# MAGIC-HOOVER-TRANS.net
KiCad netlist of a schematic drawn in EasyEDA
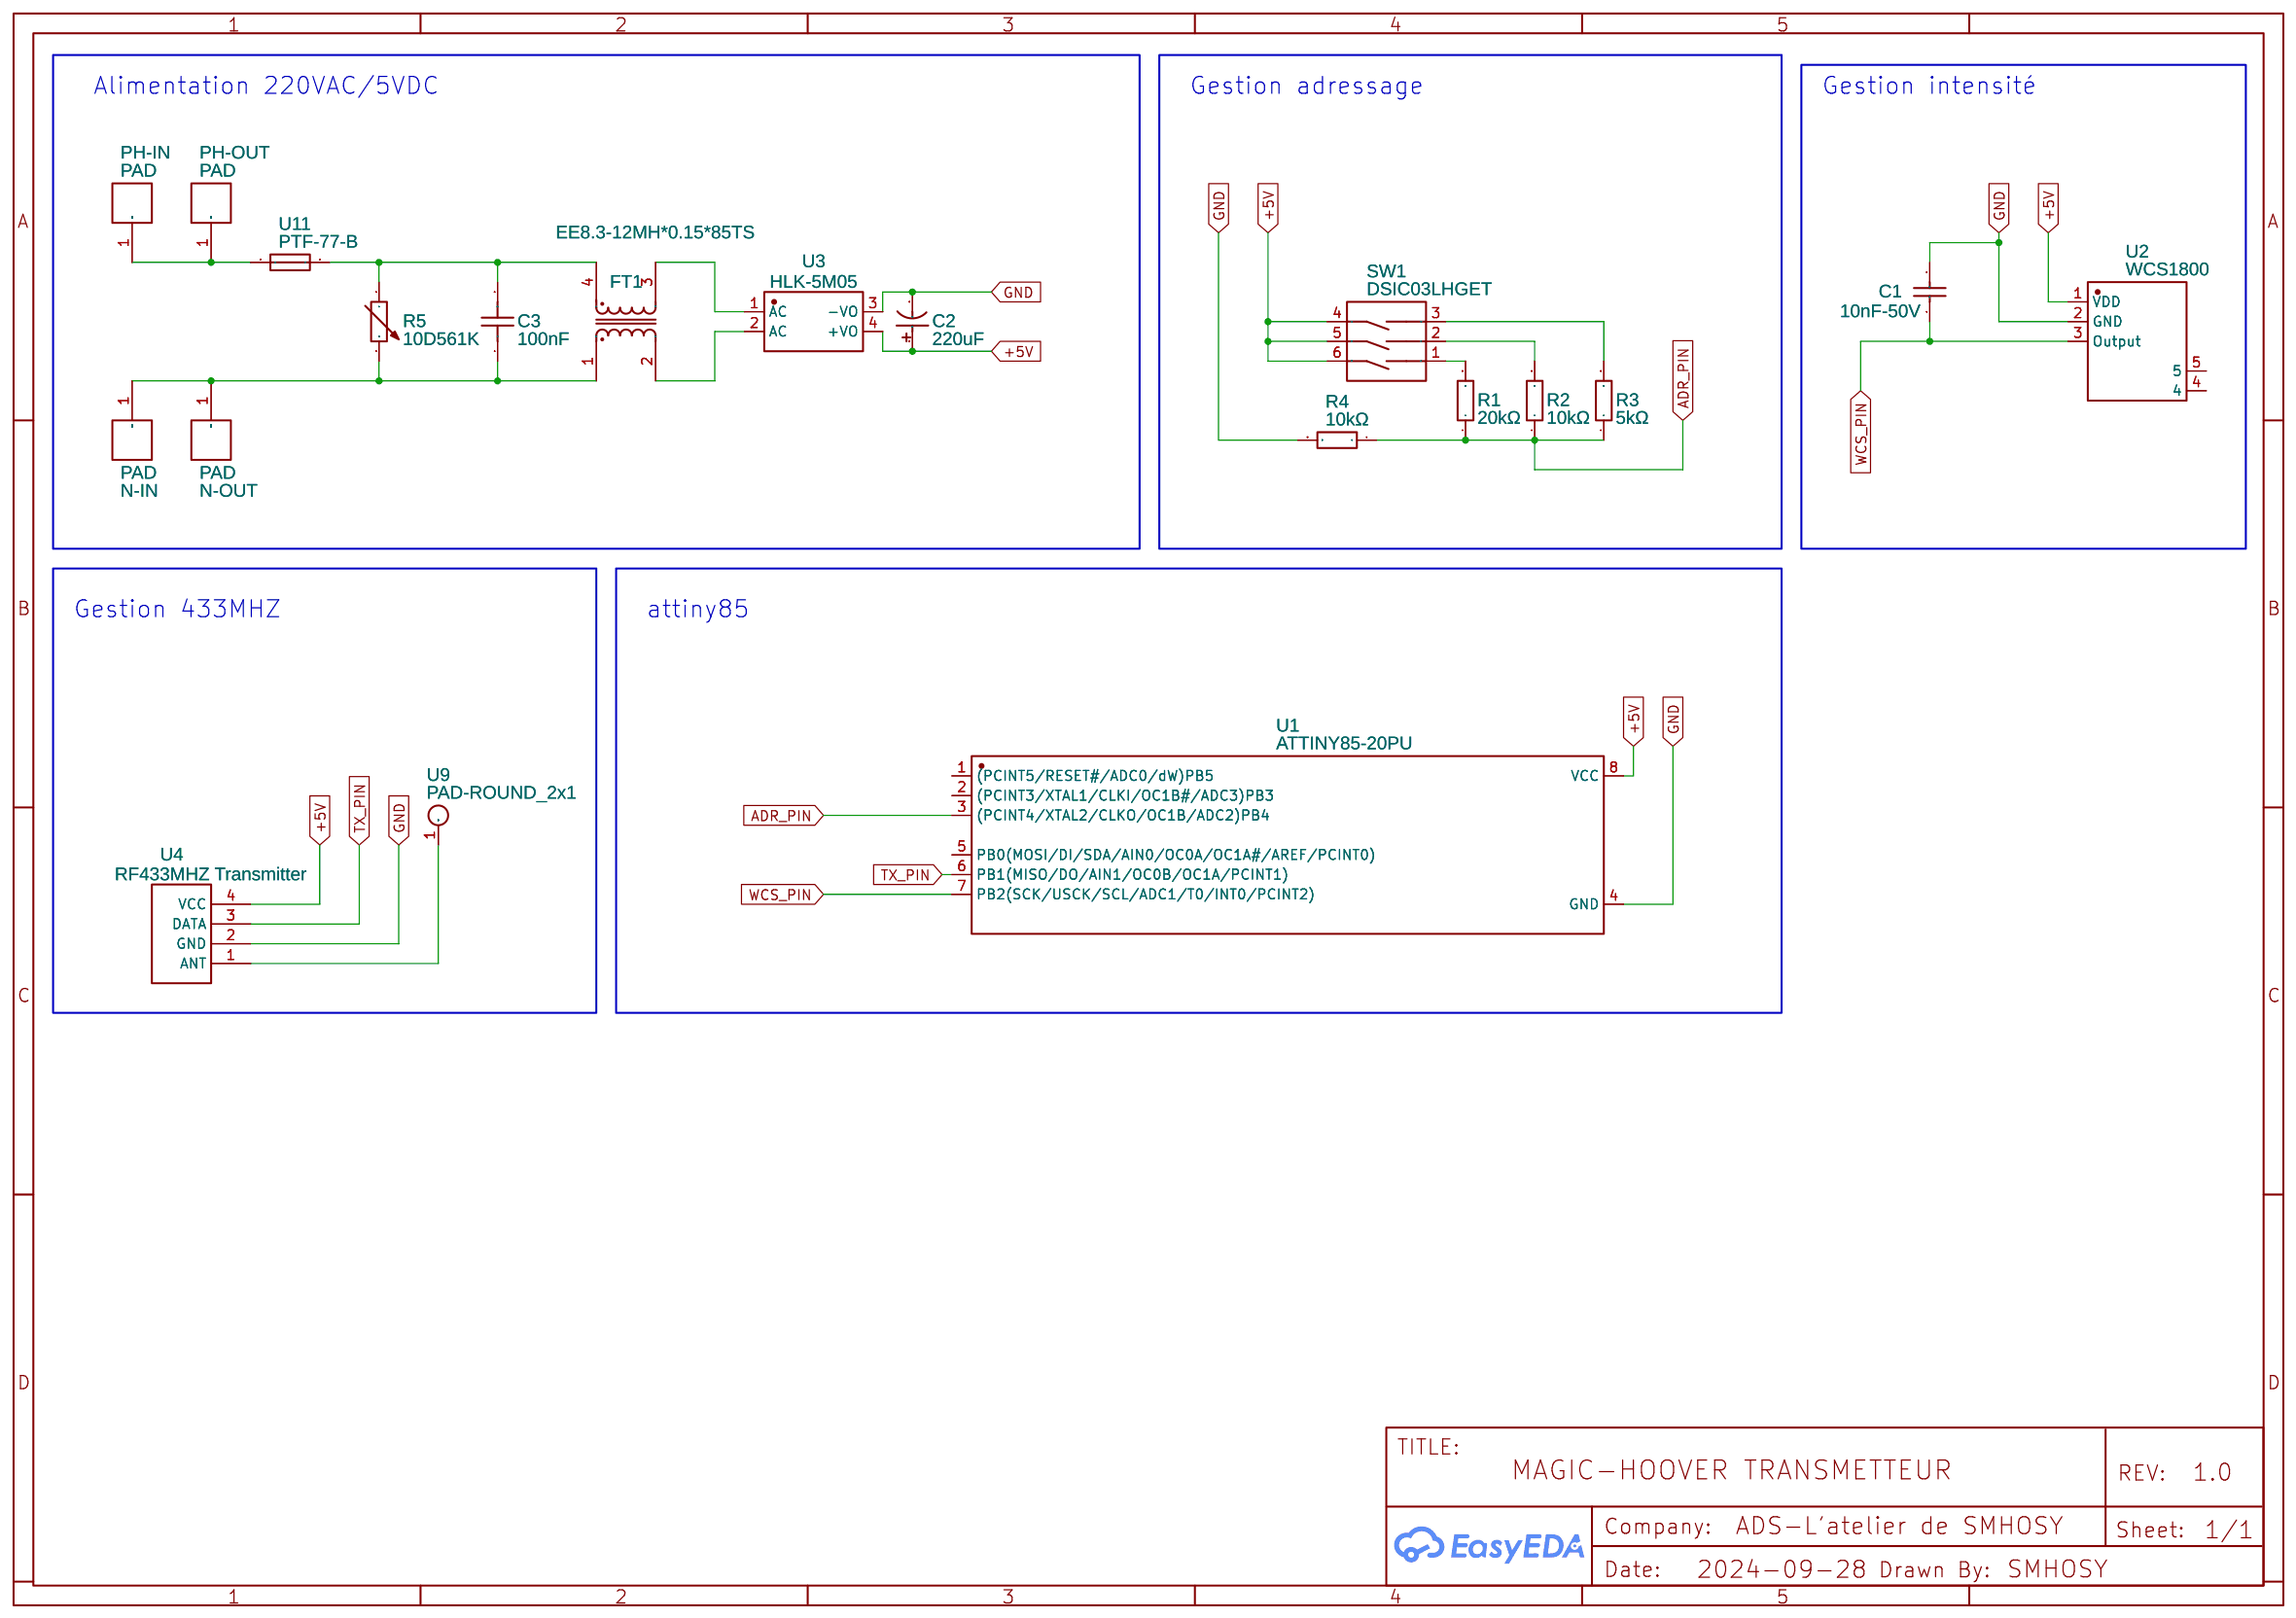
[diagram p0: schematic sheet]

(export (version "E")
  (design (tool "Eeschema 10.0.6"))
  (components
    (comp (ref "C1")
      (value "10nF-50V")
      (fields (field (name "Manufacturer Part") "C1206X103K050T") (field (name "Manufacturer") "IHHEC(禾伸堂)"))
      (libsource (lib "") (part "C1206X103K050T"))
    )
    (comp (ref "C2")
      (value "220uF")
      (fields
        (field (name "Manufacturer Part") "KM227M010D11RR0VH2FP0")
        (field (name "Manufacturer") "CX(承兴)")
      )
      (libsource (lib "") (part "220uF 10V 5*11"))
    )
    (comp (ref "C3")
      (value "100nF")
      (fields (field (name "Manufacturer Part") "X2-104K-275VAC") (field (name "Manufacturer") "NDF(达孚)"))
      (libsource (lib "") (part "X2-104K-275VAC_C914484"))
    )
    (comp (ref "FT1")
      (value "EE8.3-12MH*0.15*85TS")
      (fields (field (name "Manufacturer") "增益"))
      (libsource (lib "") (part "EE8.3-12MH*0.15*85TS"))
    )
    (comp (ref "N-IN") (value "PAD") (libsource (lib "") (part "PAD_2")))
    (comp (ref "N-OUT") (value "PAD") (libsource (lib "") (part "PAD_1")))
    (comp (ref "PH-IN") (value "PAD") (libsource (lib "") (part "PAD_3")))
    (comp (ref "PH-OUT") (value "PAD") (libsource (lib "") (part "PAD")))
    (comp (ref "R1")
      (value "20kΩ")
      (fields (field (name "Manufacturer Part") "PTFR1206B20K0P9") (field (name "Manufacturer") "RESI(开步睿思)"))
      (libsource (lib "") (part "PTFR1206B20K0P9"))
    )
    (comp (ref "R2")
      (value "10kΩ")
      (fields
        (field (name "Manufacturer Part") "QR1206J10K0P05Z")
        (field (name "Manufacturer") "EVER OHMS(天二科技)")
      )
      (libsource (lib "") (part "QR1206J10KP05"))
    )
    (comp (ref "R3")
      (value "5kΩ")
      (fields
        (field (name "Manufacturer Part") "QR1206J10K0P05Z")
        (field (name "Manufacturer") "EVER OHMS(天二科技)")
      )
      (libsource (lib "") (part "QR1206J10KP05"))
    )
    (comp (ref "R4")
      (value "10kΩ")
      (fields
        (field (name "Manufacturer Part") "QR1206J10K0P05Z")
        (field (name "Manufacturer") "EVER OHMS(天二科技)")
      )
      (libsource (lib "") (part "QR1206J10KP05_1"))
    )
    (comp (ref "R5")
      (value "10D561K")
      (fields (field (name "Manufacturer") "HEL(鸿志)"))
      (libsource (lib "") (part "10D561K"))
    )
    (comp (ref "SW1")
      (value "DSIC03LHGET")
      (fields (field (name "Manufacturer") "YE"))
      (libsource (lib "") (part "DSIC03LHGET"))
    )
    (comp (ref "U1")
      (value "ATTINY85-20PU")
      (fields (field (name "Manufacturer") "MICROCHIP(美国微芯)"))
      (libsource (lib "") (part "ATTINY85-20PU"))
    )
    (comp (ref "U2") (value "WCS1800") (libsource (lib "") (part "WCS1800")))
    (comp (ref "U3")
      (value "HLK-5M05")
      (fields (field (name "Manufacturer") "HI-LINK(海凌科)"))
      (libsource (lib "") (part "HLK-5M05"))
    )
    (comp (ref "U4") (value "RF433MHZ Transmitter") (libsource (lib "") (part "RF433MHZ Transmitter")))
    (comp (ref "U9") (value "PAD-ROUND_2x1") (libsource (lib "") (part "PAD-ROUND_2x1")))
    (comp (ref "U11")
      (value "PTF-77-B")
      (fields (field (name "Manufacturer") "XFCN(兴飞)"))
      (libsource (lib "") (part "PTF-77-B"))
    )
  )
  (nets
    (net (code "1") (name "+5V") (class "Default")
      (node (ref "C2") (pin "1") (pinfunction "1_1") (pintype "input"))
      (node (ref "SW1") (pin "4") (pinfunction "4_4") (pintype "unspecified"))
      (node (ref "SW1") (pin "5") (pinfunction "5_5") (pintype "unspecified"))
      (node (ref "SW1") (pin "6") (pinfunction "6_6") (pintype "unspecified"))
      (node (ref "U1") (pin "8") (pinfunction "VCC_8") (pintype "unspecified"))
      (node (ref "U2") (pin "1") (pinfunction "VDD_1") (pintype "unspecified"))
      (node (ref "U3") (pin "4") (pinfunction "+VO_4") (pintype "unspecified"))
      (node (ref "U4") (pin "4") (pinfunction "VCC_4") (pintype "unspecified"))
    )
    (net (code "2") (name "ADR_PIN") (class "Default")
      (node (ref "R1") (pin "1") (pinfunction "1_1") (pintype "unspecified"))
      (node (ref "R2") (pin "1") (pinfunction "1_1") (pintype "unspecified"))
      (node (ref "R3") (pin "1") (pinfunction "1_1") (pintype "unspecified"))
      (node (ref "R4") (pin "1") (pinfunction "1_1") (pintype "unspecified"))
      (node (ref "U1") (pin "3") (pinfunction "(PCINT4/XTAL2/CLKO/OC1B/ADC2)PB4_3") (pintype "unspecified"))
    )
    (net (code "3") (name "GND") (class "Default")
      (node (ref "C1") (pin "1") (pinfunction "1_1") (pintype "input"))
      (node (ref "C2") (pin "2") (pinfunction "2_2") (pintype "input"))
      (node (ref "R4") (pin "2") (pinfunction "2_2") (pintype "unspecified"))
      (node (ref "U1") (pin "4") (pinfunction "GND_4") (pintype "unspecified"))
      (node (ref "U2") (pin "2") (pinfunction "GND_2") (pintype "unspecified"))
      (node (ref "U3") (pin "3") (pinfunction "-VO_3") (pintype "unspecified"))
      (node (ref "U4") (pin "2") (pinfunction "GND_2") (pintype "unspecified"))
    )
    (net (code "4") (name "Net-(C3-Pad2)") (class "Default")
      (node (ref "C3") (pin "2") (pinfunction "2_2") (pintype "unspecified"))
      (node (ref "FT1") (pin "4") (pinfunction "4_4") (pintype "unspecified"))
      (node (ref "R5") (pin "1") (pinfunction "1_1") (pintype "unspecified"))
      (node (ref "U11") (pin "2") (pinfunction "2_2") (pintype "unspecified"))
    )
    (net (code "5") (name "Net-(FT1-Pad2)") (class "Default")
      (node (ref "FT1") (pin "2") (pinfunction "2_2") (pintype "unspecified"))
      (node (ref "U3") (pin "2") (pinfunction "AC_2") (pintype "unspecified"))
    )
    (net (code "6") (name "Net-(FT1-Pad3)") (class "Default")
      (node (ref "FT1") (pin "3") (pinfunction "3_3") (pintype "unspecified"))
      (node (ref "U3") (pin "1") (pinfunction "AC_1") (pintype "unspecified"))
    )
    (net (code "7") (name "Net-(N-IN-PADPAD123)") (class "Default")
      (node (ref "C3") (pin "1") (pinfunction "1_1") (pintype "unspecified"))
      (node (ref "FT1") (pin "1") (pinfunction "1_1") (pintype "unspecified"))
      (node (ref "N-IN") (pin "1") (pinfunction "PADPAD123_1") (pintype "unspecified"))
      (node (ref "N-OUT") (pin "1") (pinfunction "PADPAD123_1") (pintype "unspecified"))
      (node (ref "R5") (pin "2") (pinfunction "2_2") (pintype "unspecified"))
    )
    (net (code "8") (name "Net-(PH-IN-PADPAD123)") (class "Default")
      (node (ref "PH-IN") (pin "1") (pinfunction "PADPAD123_1") (pintype "unspecified"))
      (node (ref "PH-OUT") (pin "1") (pinfunction "PADPAD123_1") (pintype "unspecified"))
      (node (ref "U11") (pin "1") (pinfunction "1_1") (pintype "unspecified"))
    )
    (net (code "9") (name "Net-(R1-Pad2)") (class "Default")
      (node (ref "R1") (pin "2") (pinfunction "2_2") (pintype "unspecified"))
      (node (ref "SW1") (pin "1") (pinfunction "1_1") (pintype "unspecified"))
    )
    (net (code "10") (name "Net-(R2-Pad2)") (class "Default")
      (node (ref "R2") (pin "2") (pinfunction "2_2") (pintype "unspecified"))
      (node (ref "SW1") (pin "2") (pinfunction "2_2") (pintype "unspecified"))
    )
    (net (code "11") (name "Net-(R3-Pad2)") (class "Default")
      (node (ref "R3") (pin "2") (pinfunction "2_2") (pintype "unspecified"))
      (node (ref "SW1") (pin "3") (pinfunction "3_3") (pintype "unspecified"))
    )
    (net (code "12") (name "Net-(U4-ANT)") (class "Default")
      (node (ref "U4") (pin "1") (pinfunction "ANT_1") (pintype "unspecified"))
      (node (ref "U9") (pin "1") (pinfunction "Pad_1") (pintype "unspecified"))
    )
    (net (code "13") (name "TX_PIN") (class "Default")
      (node (ref "U1") (pin "6") (pinfunction "PB1(MISO/DO/AIN1/OC0B/OC1A/PCINT1)_6") (pintype "unspecified"))
      (node (ref "U4") (pin "3") (pinfunction "DATA_3") (pintype "unspecified"))
    )
    (net (code "14") (name "WCS_PIN") (class "Default")
      (node (ref "C1") (pin "2") (pinfunction "2_2") (pintype "input"))
      (node (ref "U1") (pin "7") (pinfunction "PB2(SCK/USCK/SCL/ADC1/T0/INT0/PCINT2)_7") (pintype "unspecified"))
      (node (ref "U2") (pin "3") (pinfunction "Output_3") (pintype "unspecified"))
    )
    (net (code "15") (name "unconnected-(U1-(PCINT3{slash}XTAL1{slash}CLKI{slash}OC1B#{slash}ADC3)PB3-Pad2)") (class "Default")
      (node (ref "U1") (pin "2") (pinfunction "(PCINT3/XTAL1/CLKI/OC1B#/ADC3)PB3_2") (pintype "unspecified"))
    )
    (net (code "16") (name "unconnected-(U1-(PCINT5{slash}RESET#{slash}ADC0{slash}dW)PB5-Pad1)") (class "Default")
      (node (ref "U1") (pin "1") (pinfunction "(PCINT5/RESET#/ADC0/dW)PB5_1") (pintype "unspecified"))
    )
    (net (code "17") (name "unconnected-(U1-PB0(MOSI{slash}DI{slash}SDA{slash}AIN0{slash}OC0A{slash}OC1A#{slash}AREF{slash}PCINT0)-Pad5)") (class "Default")
      (node (ref "U1") (pin "5") (pinfunction "PB0(MOSI/DI/SDA/AIN0/OC0A/OC1A#/AREF/PCINT0)_5") (pintype "unspecified"))
    )
    (net (code "18") (name "unconnected-(U2-Pad4)") (class "Default")
      (node (ref "U2") (pin "4") (pinfunction "4_4") (pintype "unspecified"))
    )
    (net (code "19") (name "unconnected-(U2-Pad5)") (class "Default")
      (node (ref "U2") (pin "5") (pinfunction "5_5") (pintype "unspecified"))
    )
  )
)
